# a111-fader.net
KiCad netlist of a schematic drawn in EAGLE
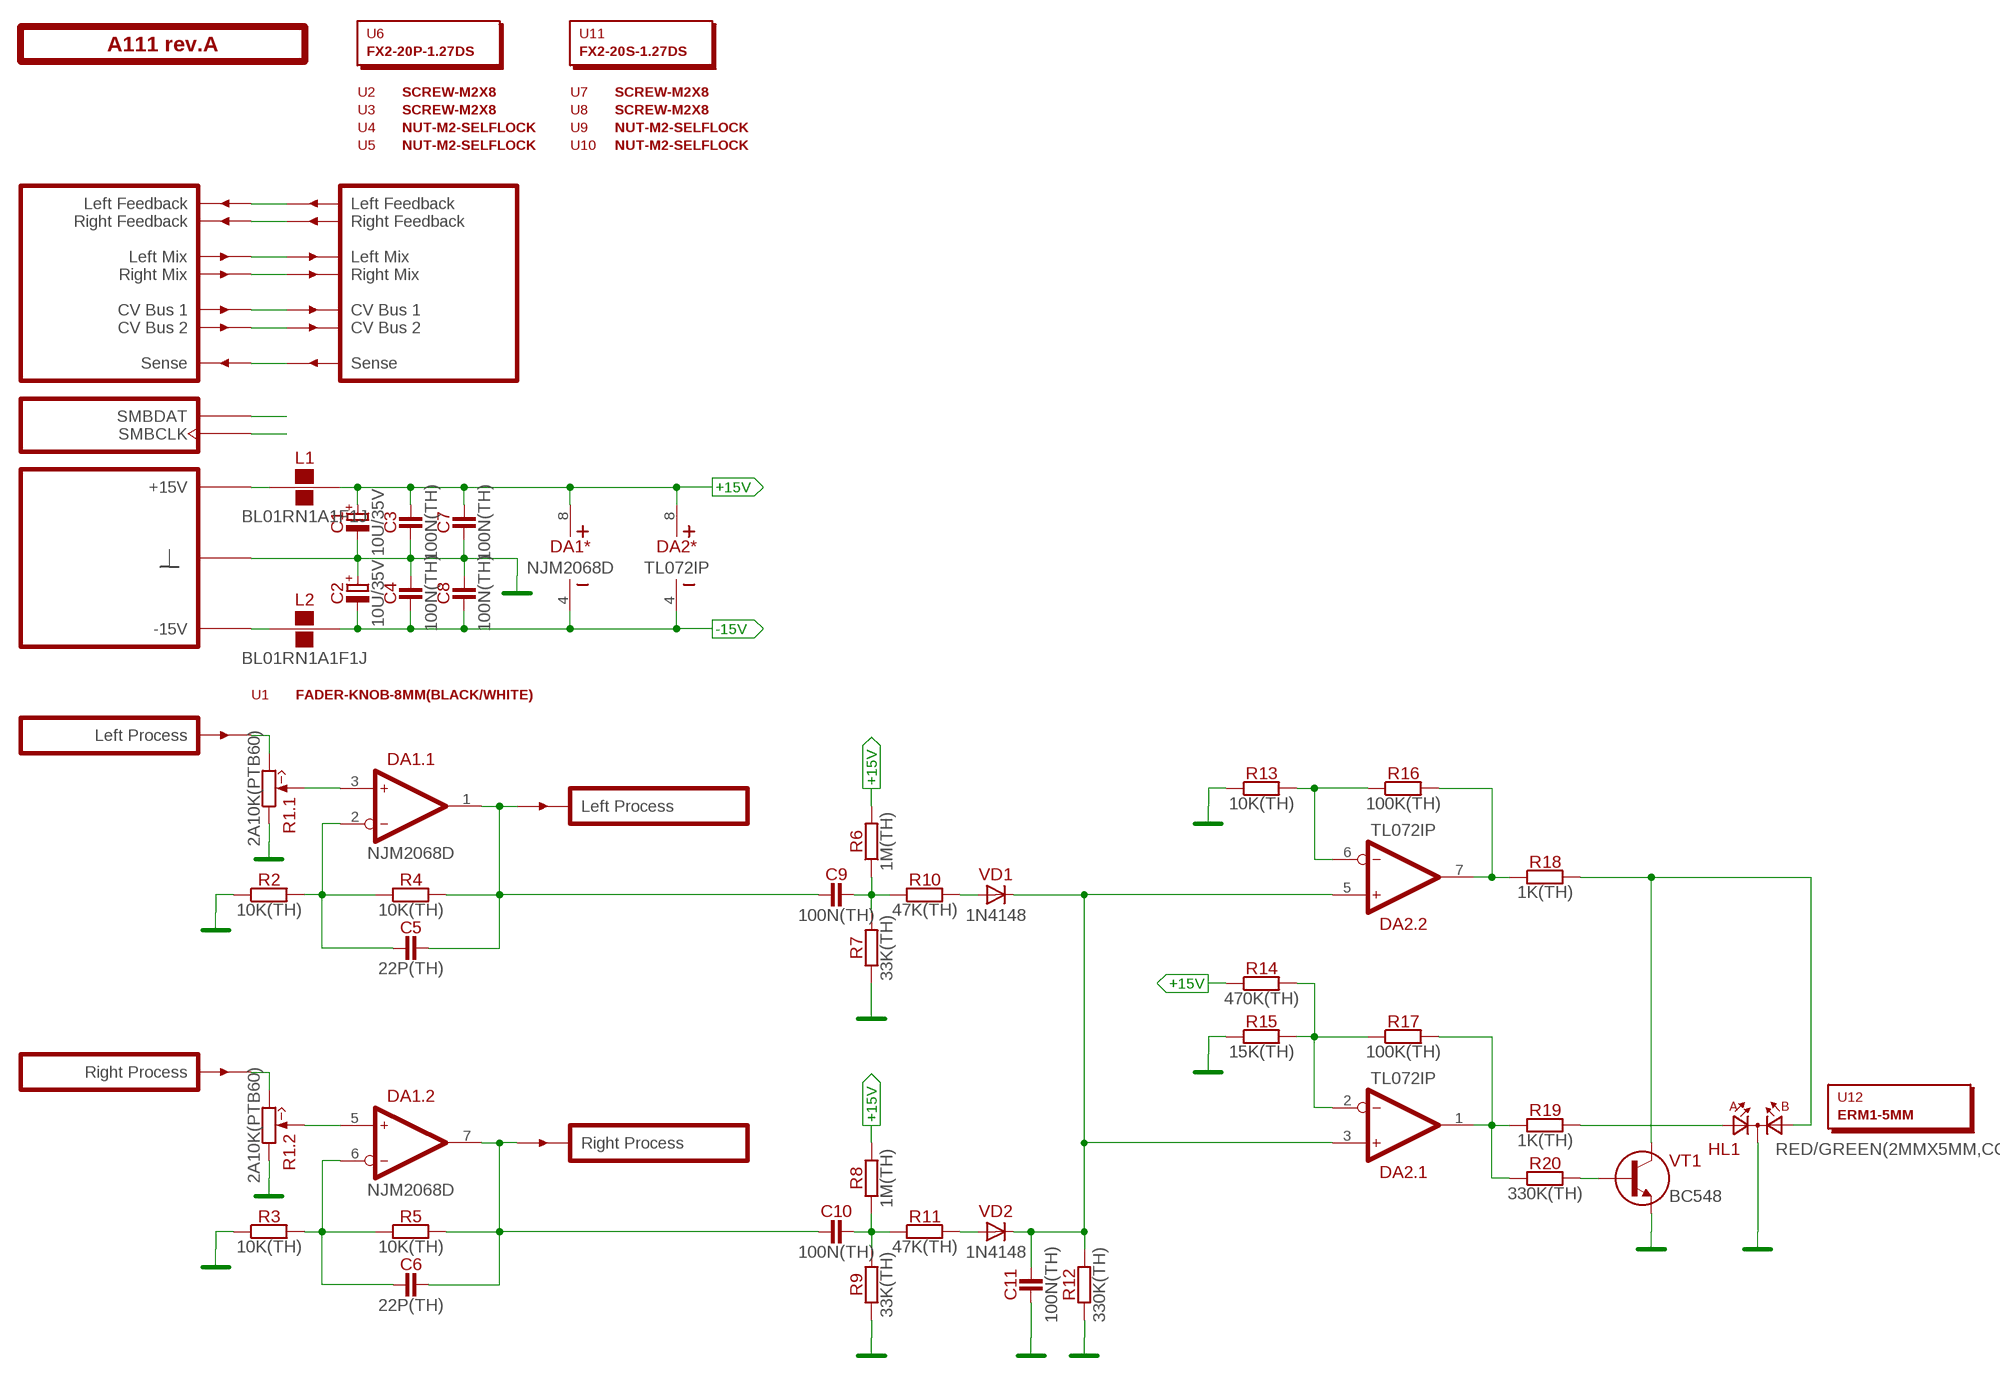
[diagram p0: schematic, sheet 1]

(export (version "E")
  (design (tool "Eeschema 10.0.6"))
  (components
    (comp (ref "C1")
      (value "10U/35V")
      (footprint "eagle-import:E2-5")
      (libsource (lib "eagle-import") (part "?10U/35V"))
    )
    (comp (ref "C2")
      (value "10U/35V")
      (footprint "eagle-import:E2-5")
      (libsource (lib "eagle-import") (part "?10U/35V"))
    )
    (comp (ref "C3")
      (value "100N(TH)")
      (footprint "eagle-import:C050-024X044")
      (libsource (lib "eagle-import") (part "?100N(TH)"))
    )
    (comp (ref "C4")
      (value "100N(TH)")
      (footprint "eagle-import:C050-024X044")
      (libsource (lib "eagle-import") (part "?100N(TH)"))
    )
    (comp (ref "C5")
      (value "22P(TH)")
      (footprint "eagle-import:C050-024X044")
      (libsource (lib "eagle-import") (part "?22P(TH)"))
    )
    (comp (ref "C6")
      (value "22P(TH)")
      (footprint "eagle-import:C050-024X044")
      (libsource (lib "eagle-import") (part "?22P(TH)"))
    )
    (comp (ref "C7")
      (value "100N(TH)")
      (footprint "eagle-import:C050-024X044")
      (libsource (lib "eagle-import") (part "?100N(TH)"))
    )
    (comp (ref "C8")
      (value "100N(TH)")
      (footprint "eagle-import:C050-024X044")
      (libsource (lib "eagle-import") (part "?100N(TH)"))
    )
    (comp (ref "C9")
      (value "100N(TH)")
      (footprint "eagle-import:C050-024X044")
      (libsource (lib "eagle-import") (part "?100N(TH)"))
    )
    (comp (ref "C10")
      (value "100N(TH)")
      (footprint "eagle-import:C050-024X044")
      (libsource (lib "eagle-import") (part "?100N(TH)"))
    )
    (comp (ref "C11")
      (value "100N(TH)")
      (footprint "eagle-import:C050-024X044")
      (libsource (lib "eagle-import") (part "?100N(TH)"))
    )
    (comp (ref "DA1")
      (value "NJM2068D")
      (footprint "eagle-import:DIP-8")
      (libsource (lib "eagle-import") (part "NJM2068D"))
    )
    (comp (ref "DA2")
      (value "TL072IP")
      (footprint "eagle-import:DIP-8")
      (libsource (lib "eagle-import") (part "TL072IP"))
    )
    (comp (ref "HL1")
      (value "RED/GREEN(2MMX5MM,CC)")
      (footprint "eagle-import:LED2X5-3PIN")
      (libsource (lib "eagle-import") (part "?(2MMX5MM,CC)RED/GREEN"))
    )
    (comp (ref "L1")
      (value "BL01RN1A1F1J")
      (footprint "eagle-import:BL01RN1A")
      (libsource (lib "eagle-import") (part "BL01RN1A?1F1J"))
    )
    (comp (ref "L2")
      (value "BL01RN1A1F1J")
      (footprint "eagle-import:BL01RN1A")
      (libsource (lib "eagle-import") (part "BL01RN1A?1F1J"))
    )
    (comp (ref "PCB1")
      (value "A111 rev.A")
      (footprint "eagle-import:ST2-BOARD-50")
      (libsource (lib "eagle-import") (part "ST2-BOARD-?50"))
    )
    (comp (ref "R1")
      (value "2A10K(PTB60)")
      (footprint "eagle-import:PTB6044")
      (libsource (lib "eagle-import") (part "2?(PTB60)A10K"))
    )
    (comp (ref "R2")
      (value "10K(TH)")
      (footprint "eagle-import:R-0207_10")
      (libsource (lib "eagle-import") (part "?10K(TH)"))
    )
    (comp (ref "R3")
      (value "10K(TH)")
      (footprint "eagle-import:R-0207_10")
      (libsource (lib "eagle-import") (part "?10K(TH)"))
    )
    (comp (ref "R4")
      (value "10K(TH)")
      (footprint "eagle-import:R-0207_10")
      (libsource (lib "eagle-import") (part "?10K(TH)"))
    )
    (comp (ref "R5")
      (value "10K(TH)")
      (footprint "eagle-import:R-0207_10")
      (libsource (lib "eagle-import") (part "?10K(TH)"))
    )
    (comp (ref "R6")
      (value "1M(TH)")
      (footprint "eagle-import:R-0207_10")
      (libsource (lib "eagle-import") (part "?1M(TH)"))
    )
    (comp (ref "R7")
      (value "33K(TH)")
      (footprint "eagle-import:R-0207_10")
      (libsource (lib "eagle-import") (part "?33K(TH)"))
    )
    (comp (ref "R8")
      (value "1M(TH)")
      (footprint "eagle-import:R-0207_10")
      (libsource (lib "eagle-import") (part "?1M(TH)"))
    )
    (comp (ref "R9")
      (value "33K(TH)")
      (footprint "eagle-import:R-0207_10")
      (libsource (lib "eagle-import") (part "?33K(TH)"))
    )
    (comp (ref "R10")
      (value "47K(TH)")
      (footprint "eagle-import:R-0207_10")
      (libsource (lib "eagle-import") (part "?47K(TH)"))
    )
    (comp (ref "R11")
      (value "47K(TH)")
      (footprint "eagle-import:R-0207_10")
      (libsource (lib "eagle-import") (part "?47K(TH)"))
    )
    (comp (ref "R12")
      (value "330K(TH)")
      (footprint "eagle-import:R-0207_10")
      (libsource (lib "eagle-import") (part "?330K(TH)"))
    )
    (comp (ref "R13")
      (value "10K(TH)")
      (footprint "eagle-import:R-0207_10")
      (libsource (lib "eagle-import") (part "?10K(TH)"))
    )
    (comp (ref "R14")
      (value "470K(TH)")
      (footprint "eagle-import:R-0207_10")
      (libsource (lib "eagle-import") (part "?470K(TH)"))
    )
    (comp (ref "R15")
      (value "15K(TH)")
      (footprint "eagle-import:R-0207_10")
      (libsource (lib "eagle-import") (part "?15K(TH)"))
    )
    (comp (ref "R16")
      (value "100K(TH)")
      (footprint "eagle-import:R-0207_10")
      (libsource (lib "eagle-import") (part "?100K(TH)"))
    )
    (comp (ref "R17")
      (value "100K(TH)")
      (footprint "eagle-import:R-0207_10")
      (libsource (lib "eagle-import") (part "?100K(TH)"))
    )
    (comp (ref "R18")
      (value "1K(TH)")
      (footprint "eagle-import:R-0207_10")
      (libsource (lib "eagle-import") (part "?1K(TH)"))
    )
    (comp (ref "R19")
      (value "1K(TH)")
      (footprint "eagle-import:R-0207_10")
      (libsource (lib "eagle-import") (part "?1K(TH)"))
    )
    (comp (ref "R20")
      (value "330K(TH)")
      (footprint "eagle-import:R-0207_10")
      (libsource (lib "eagle-import") (part "?330K(TH)"))
    )
    (comp (ref "U1")
      (value "FADER-KNOB-8MM(BLACK/WHITE)")
      (footprint "eagle-import:EMPTY")
      (libsource (lib "eagle-import") (part "?FADER-KNOB-8MM(BLACK/WHITE)"))
    )
    (comp (ref "U2")
      (value "SCREW-M2X8")
      (footprint "eagle-import:EMPTY")
      (libsource (lib "eagle-import") (part "?SCREW-M2X8"))
    )
    (comp (ref "U3")
      (value "SCREW-M2X8")
      (footprint "eagle-import:EMPTY")
      (libsource (lib "eagle-import") (part "?SCREW-M2X8"))
    )
    (comp (ref "U4")
      (value "NUT-M2-SELFLOCK")
      (footprint "eagle-import:EMPTY")
      (libsource (lib "eagle-import") (part "?NUT-M2-SELFLOCK"))
    )
    (comp (ref "U5")
      (value "NUT-M2-SELFLOCK")
      (footprint "eagle-import:EMPTY")
      (libsource (lib "eagle-import") (part "?NUT-M2-SELFLOCK"))
    )
    (comp (ref "U6")
      (value "FX2-20P-1.27DS")
      (footprint "eagle-import:EMPTY")
      (libsource (lib "eagle-import") (part "?FX2-20P-1.27DS"))
    )
    (comp (ref "U7")
      (value "SCREW-M2X8")
      (footprint "eagle-import:EMPTY")
      (libsource (lib "eagle-import") (part "?SCREW-M2X8"))
    )
    (comp (ref "U8")
      (value "SCREW-M2X8")
      (footprint "eagle-import:EMPTY")
      (libsource (lib "eagle-import") (part "?SCREW-M2X8"))
    )
    (comp (ref "U9")
      (value "NUT-M2-SELFLOCK")
      (footprint "eagle-import:EMPTY")
      (libsource (lib "eagle-import") (part "?NUT-M2-SELFLOCK"))
    )
    (comp (ref "U10")
      (value "NUT-M2-SELFLOCK")
      (footprint "eagle-import:EMPTY")
      (libsource (lib "eagle-import") (part "?NUT-M2-SELFLOCK"))
    )
    (comp (ref "U11")
      (value "FX2-20S-1.27DS")
      (footprint "eagle-import:EMPTY")
      (libsource (lib "eagle-import") (part "?FX2-20S-1.27DS"))
    )
    (comp (ref "U12")
      (value "ERM1-5MM")
      (footprint "eagle-import:EMPTY")
      (libsource (lib "eagle-import") (part "?ERM1-5MM"))
    )
    (comp (ref "VD1")
      (value "1N4148")
      (footprint "eagle-import:DO35-7")
      (libsource (lib "eagle-import") (part "?1N4148"))
    )
    (comp (ref "VD2")
      (value "1N4148")
      (footprint "eagle-import:DO35-7")
      (libsource (lib "eagle-import") (part "?1N4148"))
    )
    (comp (ref "VT1")
      (value "BC548")
      (footprint "eagle-import:TO92")
      (libsource (lib "eagle-import") (part "?BC548"))
    )
  )
  (nets
    (net (code "1") (name "+15V") (class "Default")
      (node (ref "C1") (pin "+") (pinfunction "+_+") (pintype "passive"))
      (node (ref "C3") (pin "2") (pinfunction "2_2") (pintype "passive"))
      (node (ref "C7") (pin "2") (pinfunction "2_2") (pintype "passive"))
      (node (ref "DA1") (pin "8") (pinfunction "V+_8") (pintype "power_in"))
      (node (ref "DA2") (pin "8") (pinfunction "V+_8") (pintype "power_in"))
      (node (ref "L1") (pin "2") (pinfunction "2_2") (pintype "passive"))
      (node (ref "R14") (pin "1") (pinfunction "1_1") (pintype "passive"))
      (node (ref "R6") (pin "2") (pinfunction "2_2") (pintype "passive"))
      (node (ref "R8") (pin "2") (pinfunction "2_2") (pintype "passive"))
    )
    (net (code "2") (name "-15V") (class "Default")
      (node (ref "C2") (pin "-") (pinfunction "-_-") (pintype "passive"))
      (node (ref "C4") (pin "1") (pinfunction "1_1") (pintype "passive"))
      (node (ref "C8") (pin "1") (pinfunction "1_1") (pintype "passive"))
      (node (ref "DA1") (pin "4") (pinfunction "V-_4") (pintype "power_in"))
      (node (ref "DA2") (pin "4") (pinfunction "V-_4") (pintype "power_in"))
      (node (ref "L2") (pin "2") (pinfunction "2_2") (pintype "passive"))
    )
    (net (code "3") (name "GND") (class "Default")
      (node (ref "C1") (pin "-") (pinfunction "-_-") (pintype "passive"))
      (node (ref "C11") (pin "1") (pinfunction "1_1") (pintype "passive"))
      (node (ref "C2") (pin "+") (pinfunction "+_+") (pintype "passive"))
      (node (ref "C3") (pin "1") (pinfunction "1_1") (pintype "passive"))
      (node (ref "C4") (pin "2") (pinfunction "2_2") (pintype "passive"))
      (node (ref "C7") (pin "1") (pinfunction "1_1") (pintype "passive"))
      (node (ref "C8") (pin "2") (pinfunction "2_2") (pintype "passive"))
      (node (ref "HL1") (pin "K") (pinfunction "K_K") (pintype "passive"))
      (node (ref "PCB1") (pin "B4") (pinfunction "GND_B4") (pintype "bidirectional"))
      (node (ref "PCB1") (pin "B4'") (pinfunction "GND_B4'") (pintype "bidirectional"))
      (node (ref "PCB1") (pin "B5") (pinfunction "GND_B5") (pintype "bidirectional"))
      (node (ref "PCB1") (pin "B5'") (pinfunction "GND_B5'") (pintype "bidirectional"))
      (node (ref "PCB1") (pin "B6") (pinfunction "GND_B6") (pintype "bidirectional"))
      (node (ref "PCB1") (pin "B6'") (pinfunction "GND_B6'") (pintype "bidirectional"))
      (node (ref "PCB1") (pin "B7") (pinfunction "GND_B7") (pintype "bidirectional"))
      (node (ref "PCB1") (pin "B7'") (pinfunction "GND_B7'") (pintype "bidirectional"))
      (node (ref "PCB1") (pin "B8") (pinfunction "GND_B8") (pintype "bidirectional"))
      (node (ref "PCB1") (pin "B8'") (pinfunction "GND_B8'") (pintype "bidirectional"))
      (node (ref "R1") (pin "A1") (pinfunction "CCW_A1") (pintype "passive"))
      (node (ref "R1") (pin "B1") (pinfunction "CCW_B1") (pintype "passive"))
      (node (ref "R12") (pin "1") (pinfunction "1_1") (pintype "passive"))
      (node (ref "R13") (pin "1") (pinfunction "1_1") (pintype "passive"))
      (node (ref "R15") (pin "1") (pinfunction "1_1") (pintype "passive"))
      (node (ref "R2") (pin "1") (pinfunction "1_1") (pintype "passive"))
      (node (ref "R3") (pin "1") (pinfunction "1_1") (pintype "passive"))
      (node (ref "R7") (pin "1") (pinfunction "1_1") (pintype "passive"))
      (node (ref "R9") (pin "1") (pinfunction "1_1") (pintype "passive"))
      (node (ref "VT1") (pin "3") (pinfunction "E_3") (pintype "passive"))
    )
    (net (code "4") (name "Net-(C9-Pad2)") (class "Default")
      (node (ref "C9") (pin "2") (pinfunction "2_2") (pintype "passive"))
      (node (ref "R10") (pin "1") (pinfunction "1_1") (pintype "passive"))
      (node (ref "R6") (pin "1") (pinfunction "1_1") (pintype "passive"))
      (node (ref "R7") (pin "2") (pinfunction "2_2") (pintype "passive"))
    )
    (net (code "5") (name "Net-(C10-Pad2)") (class "Default")
      (node (ref "C10") (pin "2") (pinfunction "2_2") (pintype "passive"))
      (node (ref "R11") (pin "1") (pinfunction "1_1") (pintype "passive"))
      (node (ref "R8") (pin "1") (pinfunction "1_1") (pintype "passive"))
      (node (ref "R9") (pin "2") (pinfunction "2_2") (pintype "passive"))
    )
    (net (code "6") (name "Net-(DA1B-IN+)") (class "Default")
      (node (ref "DA1") (pin "3") (pinfunction "IN+_3") (pintype "input"))
      (node (ref "R1") (pin "A2") (pinfunction "W_A2") (pintype "passive"))
    )
    (net (code "7") (name "Net-(DA1B-IN-)") (class "Default")
      (node (ref "C5") (pin "1") (pinfunction "1_1") (pintype "passive"))
      (node (ref "DA1") (pin "2") (pinfunction "IN-_2") (pintype "input"))
      (node (ref "R2") (pin "2") (pinfunction "2_2") (pintype "passive"))
      (node (ref "R4") (pin "1") (pinfunction "1_1") (pintype "passive"))
    )
    (net (code "8") (name "Net-(DA1B-OUT)") (class "Default")
      (node (ref "C5") (pin "2") (pinfunction "2_2") (pintype "passive"))
      (node (ref "C9") (pin "1") (pinfunction "1_1") (pintype "passive"))
      (node (ref "DA1") (pin "1") (pinfunction "OUT_1") (pintype "output"))
      (node (ref "PCB1") (pin "BOUTL'") (pinfunction "OUTL_BOUTL'") (pintype "bidirectional"))
      (node (ref "R4") (pin "2") (pinfunction "2_2") (pintype "passive"))
    )
    (net (code "9") (name "Net-(DA1C-IN+)") (class "Default")
      (node (ref "DA1") (pin "5") (pinfunction "IN+_5") (pintype "input"))
      (node (ref "R1") (pin "B2") (pinfunction "W_B2") (pintype "passive"))
    )
    (net (code "10") (name "Net-(DA1C-IN-)") (class "Default")
      (node (ref "C6") (pin "1") (pinfunction "1_1") (pintype "passive"))
      (node (ref "DA1") (pin "6") (pinfunction "IN-_6") (pintype "input"))
      (node (ref "R3") (pin "2") (pinfunction "2_2") (pintype "passive"))
      (node (ref "R5") (pin "1") (pinfunction "1_1") (pintype "passive"))
    )
    (net (code "11") (name "Net-(DA1C-OUT)") (class "Default")
      (node (ref "C10") (pin "1") (pinfunction "1_1") (pintype "passive"))
      (node (ref "C6") (pin "2") (pinfunction "2_2") (pintype "passive"))
      (node (ref "DA1") (pin "7") (pinfunction "OUT_7") (pintype "output"))
      (node (ref "PCB1") (pin "BOUTR'") (pinfunction "OUTR_BOUTR'") (pintype "bidirectional"))
      (node (ref "R5") (pin "2") (pinfunction "2_2") (pintype "passive"))
    )
    (net (code "12") (name "Net-(DA2B-IN+)") (class "Default")
      (node (ref "C11") (pin "2") (pinfunction "2_2") (pintype "passive"))
      (node (ref "DA2") (pin "3") (pinfunction "IN+_3") (pintype "input"))
      (node (ref "DA2") (pin "5") (pinfunction "IN+_5") (pintype "input"))
      (node (ref "R12") (pin "2") (pinfunction "2_2") (pintype "passive"))
      (node (ref "VD1") (pin "C") (pinfunction "C_C") (pintype "passive"))
      (node (ref "VD2") (pin "C") (pinfunction "C_C") (pintype "passive"))
    )
    (net (code "13") (name "Net-(DA2B-IN-)") (class "Default")
      (node (ref "DA2") (pin "2") (pinfunction "IN-_2") (pintype "input"))
      (node (ref "R14") (pin "2") (pinfunction "2_2") (pintype "passive"))
      (node (ref "R15") (pin "2") (pinfunction "2_2") (pintype "passive"))
      (node (ref "R17") (pin "1") (pinfunction "1_1") (pintype "passive"))
    )
    (net (code "14") (name "Net-(DA2B-OUT)") (class "Default")
      (node (ref "DA2") (pin "1") (pinfunction "OUT_1") (pintype "output"))
      (node (ref "R17") (pin "2") (pinfunction "2_2") (pintype "passive"))
      (node (ref "R19") (pin "1") (pinfunction "1_1") (pintype "passive"))
      (node (ref "R20") (pin "1") (pinfunction "1_1") (pintype "passive"))
    )
    (net (code "15") (name "Net-(DA2C-IN-)") (class "Default")
      (node (ref "DA2") (pin "6") (pinfunction "IN-_6") (pintype "input"))
      (node (ref "R13") (pin "2") (pinfunction "2_2") (pintype "passive"))
      (node (ref "R16") (pin "1") (pinfunction "1_1") (pintype "passive"))
    )
    (net (code "16") (name "Net-(DA2C-OUT)") (class "Default")
      (node (ref "DA2") (pin "7") (pinfunction "OUT_7") (pintype "output"))
      (node (ref "R16") (pin "2") (pinfunction "2_2") (pintype "passive"))
      (node (ref "R18") (pin "1") (pinfunction "1_1") (pintype "passive"))
    )
    (net (code "17") (name "Net-(HL1-PadA1)") (class "Default")
      (node (ref "HL1") (pin "A1") (pinfunction "A1_A1") (pintype "passive"))
      (node (ref "R19") (pin "2") (pinfunction "2_2") (pintype "passive"))
    )
    (net (code "18") (name "Net-(L1-Pad1)") (class "Default")
      (node (ref "L1") (pin "1") (pinfunction "1_1") (pintype "passive"))
      (node (ref "PCB1") (pin "A+15") (pinfunction "P+15V_A+15") (pintype "bidirectional"))
      (node (ref "PCB1") (pin "A+15'") (pinfunction "P+15V_A+15'") (pintype "bidirectional"))
      (node (ref "PCB1") (pin "B+15") (pinfunction "P+15V_B+15") (pintype "bidirectional"))
      (node (ref "PCB1") (pin "B+15'") (pinfunction "P+15V_B+15'") (pintype "bidirectional"))
    )
    (net (code "19") (name "Net-(L2-Pad1)") (class "Default")
      (node (ref "L2") (pin "1") (pinfunction "1_1") (pintype "passive"))
      (node (ref "PCB1") (pin "A-15") (pinfunction "P-15V_A-15") (pintype "bidirectional"))
      (node (ref "PCB1") (pin "A-15'") (pinfunction "P-15V_A-15'") (pintype "bidirectional"))
      (node (ref "PCB1") (pin "B-15") (pinfunction "P-15V_B-15") (pintype "bidirectional"))
      (node (ref "PCB1") (pin "B-15'") (pinfunction "P-15V_B-15'") (pintype "bidirectional"))
    )
    (net (code "20") (name "Net-(PCB1B-INL)") (class "Default")
      (node (ref "PCB1") (pin "BINL") (pinfunction "INL_BINL") (pintype "bidirectional"))
      (node (ref "R1") (pin "A3") (pinfunction "CW_A3") (pintype "passive"))
    )
    (net (code "21") (name "Net-(PCB1C-INR)") (class "Default")
      (node (ref "PCB1") (pin "BINR") (pinfunction "INR_BINR") (pintype "bidirectional"))
      (node (ref "R1") (pin "B3") (pinfunction "CW_B3") (pintype "passive"))
    )
    (net (code "22") (name "Net-(PCB1F-CV1)") (class "Default")
      (node (ref "PCB1") (pin "ACV1") (pinfunction "CV1_ACV1") (pintype "bidirectional"))
      (node (ref "PCB1") (pin "ACV1'") (pinfunction "CV1'_ACV1'") (pintype "bidirectional"))
    )
    (net (code "23") (name "Net-(PCB1F-CV2)") (class "Default")
      (node (ref "PCB1") (pin "ACV2") (pinfunction "CV2_ACV2") (pintype "bidirectional"))
      (node (ref "PCB1") (pin "ACV2'") (pinfunction "CV2'_ACV2'") (pintype "bidirectional"))
    )
    (net (code "24") (name "Net-(PCB1F-LFBK)") (class "Default")
      (node (ref "PCB1") (pin "ALFBK") (pinfunction "LFBK_ALFBK") (pintype "bidirectional"))
      (node (ref "PCB1") (pin "ALFBK'") (pinfunction "LFBK'_ALFBK'") (pintype "bidirectional"))
    )
    (net (code "25") (name "Net-(PCB1F-LMIX)") (class "Default")
      (node (ref "PCB1") (pin "ALMIX") (pinfunction "LMIX_ALMIX") (pintype "bidirectional"))
      (node (ref "PCB1") (pin "ALMIX'") (pinfunction "LMIX'_ALMIX'") (pintype "bidirectional"))
    )
    (net (code "26") (name "Net-(PCB1F-RFBK)") (class "Default")
      (node (ref "PCB1") (pin "ARFBK") (pinfunction "RFBK_ARFBK") (pintype "bidirectional"))
      (node (ref "PCB1") (pin "ARFBK'") (pinfunction "RFBK'_ARFBK'") (pintype "bidirectional"))
    )
    (net (code "27") (name "Net-(PCB1F-RMIX)") (class "Default")
      (node (ref "PCB1") (pin "ARMIX") (pinfunction "RMIX_ARMIX") (pintype "bidirectional"))
      (node (ref "PCB1") (pin "ARMIX'") (pinfunction "RMIX'_ARMIX'") (pintype "bidirectional"))
    )
    (net (code "28") (name "Net-(PCB1F-SENSE)") (class "Default")
      (node (ref "PCB1") (pin "BSENSE") (pinfunction "SENSE_BSENSE") (pintype "bidirectional"))
      (node (ref "PCB1") (pin "BSENSE'") (pinfunction "SENSE'_BSENSE'") (pintype "bidirectional"))
    )
    (net (code "29") (name "Net-(PCB1H-SMBCLK-PadASMBCLK')") (class "Default")
      (node (ref "PCB1") (pin "ASMBCLK") (pinfunction "SMBCLK_ASMBCLK") (pintype "bidirectional"))
      (node (ref "PCB1") (pin "ASMBCLK'") (pinfunction "SMBCLK_ASMBCLK'") (pintype "bidirectional"))
    )
    (net (code "30") (name "Net-(PCB1H-SMBDAT-PadASMBDAT')") (class "Default")
      (node (ref "PCB1") (pin "ASMBDAT") (pinfunction "SMBDAT_ASMBDAT") (pintype "bidirectional"))
      (node (ref "PCB1") (pin "ASMBDAT'") (pinfunction "SMBDAT_ASMBDAT'") (pintype "bidirectional"))
    )
    (net (code "31") (name "Net-(R10-Pad2)") (class "Default")
      (node (ref "R10") (pin "2") (pinfunction "2_2") (pintype "passive"))
      (node (ref "VD1") (pin "A") (pinfunction "A_A") (pintype "passive"))
    )
    (net (code "32") (name "Net-(R11-Pad2)") (class "Default")
      (node (ref "R11") (pin "2") (pinfunction "2_2") (pintype "passive"))
      (node (ref "VD2") (pin "A") (pinfunction "A_A") (pintype "passive"))
    )
    (net (code "33") (name "Net-(VT1-B)") (class "Default")
      (node (ref "R20") (pin "2") (pinfunction "2_2") (pintype "passive"))
      (node (ref "VT1") (pin "2") (pinfunction "B_2") (pintype "passive"))
    )
    (net (code "34") (name "Net-(VT1-C)") (class "Default")
      (node (ref "HL1") (pin "A2") (pinfunction "A2_A2") (pintype "passive"))
      (node (ref "R18") (pin "2") (pinfunction "2_2") (pintype "passive"))
      (node (ref "VT1") (pin "1") (pinfunction "C_1") (pintype "passive"))
    )
  )
)
